# 11_MT7688AN_Ethernet.net
KiCad netlist of a schematic drawn in Altium Designer
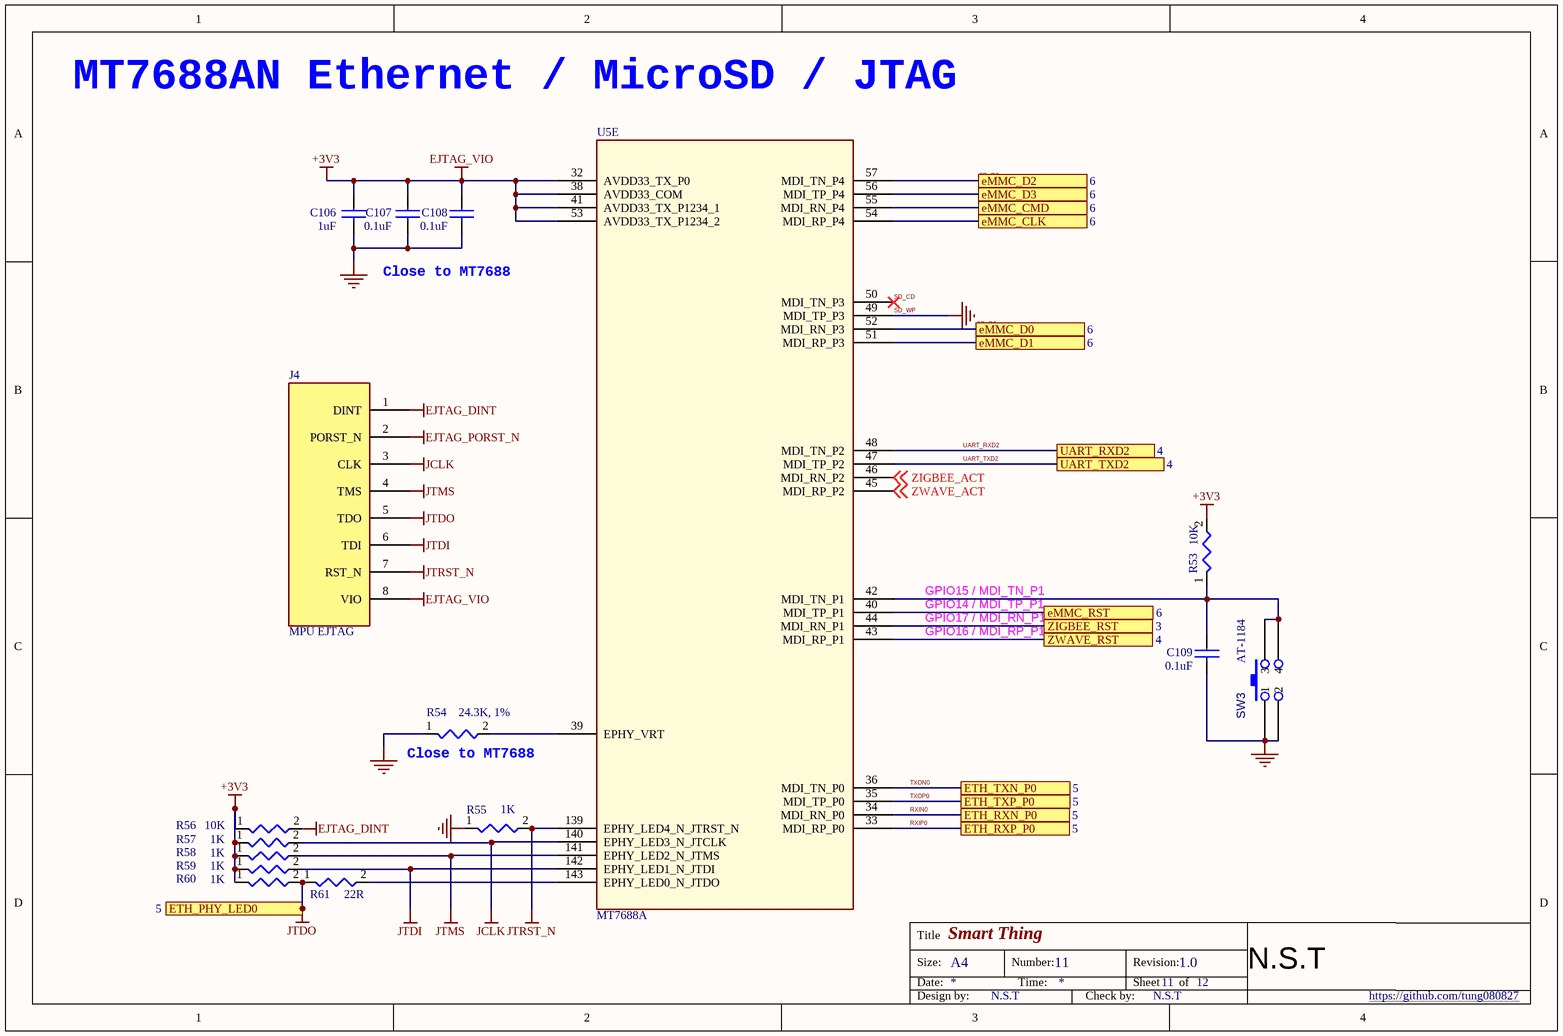
[diagram p0: 11. MT7688AN Ethernet.SchDoc]

(export (version "E")
  (design (tool "Eeschema 10.0.6"))
  (components
    (comp (ref "C106")
      (value "1uF")
      (footprint "CAPC1005X60X30NL05T10")
      (libsource (lib "MT7688AN") (part "CAP NP"))
    )
    (comp (ref "C107")
      (value "0.1uF")
      (footprint "CAPC1005X60X30NL05T10")
      (libsource (lib "MT7688AN") (part "CAP NP"))
    )
    (comp (ref "C108")
      (value "0.1uF")
      (footprint "CAPC1005X60X30NL05T10")
      (libsource (lib "MT7688AN") (part "CAP NP"))
    )
    (comp (ref "C109")
      (value "0.1uF")
      (footprint "CAPC1005X60X30NL05T10")
      (libsource (lib "MT7688AN") (part "CAP NP"))
    )
    (comp (ref "J4")
      (value "MPU EJTAG")
      (footprint "MPU EJTAG DEBUG")
      (libsource (lib "MT7688AN") (part "MPU EJTAG"))
    )
    (comp (ref "R53")
      (value "10K")
      (footprint "RESC1005X35X25NL10T10")
      (libsource (lib "MT7688AN") (part "RES/0402_3"))
    )
    (comp (ref "R54")
      (value "24.3K, 1%")
      (footprint "RESC1005X35X25NL10T10")
      (libsource (lib "MT7688AN") (part "RES/0402_3"))
    )
    (comp (ref "R55")
      (value "1K")
      (footprint "RESC1005X35X25NL10T10")
      (libsource (lib "MT7688AN") (part "RES/0402_3"))
    )
    (comp (ref "R56")
      (value "10K")
      (footprint "RESC1005X35X25NL10T10")
      (libsource (lib "MT7688AN") (part "RES/0402_3"))
    )
    (comp (ref "R57")
      (value "1K")
      (footprint "RESC1005X35X25NL10T10")
      (libsource (lib "MT7688AN") (part "RES/0402_3"))
    )
    (comp (ref "R58")
      (value "1K")
      (footprint "RESC1005X35X25NL10T10")
      (libsource (lib "MT7688AN") (part "RES/0402_3"))
    )
    (comp (ref "R59")
      (value "1K")
      (footprint "RESC1005X35X25NL10T10")
      (libsource (lib "MT7688AN") (part "RES/0402_3"))
    )
    (comp (ref "R60")
      (value "1K")
      (footprint "RESC1005X35X25NL10T10")
      (libsource (lib "MT7688AN") (part "RES/0402_3"))
    )
    (comp (ref "R61")
      (value "22R")
      (footprint "RESC1005X35X25NL10T10")
      (libsource (lib "MT7688AN") (part "RES/0402_3"))
    )
    (comp (ref "SW3")
      (value "AT-1184")
      (footprint "AT-1184 SW")
      (description "TACT Switch, H=1.5mm")
      (fields (field (name "MANUFACTURER") "Panasonic - ECG"))
      (libsource (lib "MT7688AN") (part "SW"))
    )
    (comp (ref "U5")
      (value "MT7688A")
      (footprint "MT7628AN$2F$DRQFN156$2F$SMD$2F$P0.5$2F$12X12")
      (libsource (lib "MT7688AN") (part "MT7620N-n_26"))
    )
  )
  (nets
    (net (code "1") (name "+3V3") (class "Default")
      (node (ref "C106") (pin "1") (pinfunction "1_1") (pintype "passive"))
      (node (ref "C107") (pin "1") (pinfunction "1_1") (pintype "passive"))
      (node (ref "C108") (pin "1") (pinfunction "1_1") (pintype "passive"))
      (node (ref "J4") (pin "8") (pinfunction "VIO_8") (pintype "passive"))
      (node (ref "R53") (pin "2") (pinfunction "2_2") (pintype "passive"))
      (node (ref "R56") (pin "1") (pinfunction "1_1") (pintype "passive"))
      (node (ref "R57") (pin "1") (pinfunction "1_1") (pintype "passive"))
      (node (ref "R58") (pin "1") (pinfunction "1_1") (pintype "passive"))
      (node (ref "R59") (pin "1") (pinfunction "1_1") (pintype "passive"))
      (node (ref "R60") (pin "1") (pinfunction "1_1") (pintype "passive"))
      (node (ref "U5") (pin "32") (pinfunction "AVDD33_TX_P0_32") (pintype "power_in"))
      (node (ref "U5") (pin "38") (pinfunction "AVDD33_COM_38") (pintype "power_in"))
      (node (ref "U5") (pin "41") (pinfunction "AVDD33_TX_P1234_1_41") (pintype "power_in"))
      (node (ref "U5") (pin "53") (pinfunction "AVDD33_TX_P1234_2_53") (pintype "power_in"))
    )
    (net (code "2") (name "/GPIO14 {slash} MDI_TP_P1") (class "Default")
      (node (ref "U5") (pin "40") (pinfunction "MDI_TP_P1_40") (pintype "passive"))
    )
    (net (code "3") (name "/GPIO15 {slash} MDI_TN_P1") (class "Default")
      (node (ref "C109") (pin "1") (pinfunction "1_1") (pintype "passive"))
      (node (ref "R53") (pin "1") (pinfunction "1_1") (pintype "passive"))
      (node (ref "SW3") (pin "3") (pinfunction "3_3") (pintype "passive"))
      (node (ref "SW3") (pin "4") (pinfunction "4_4") (pintype "passive"))
      (node (ref "U5") (pin "42") (pinfunction "MDI_TN_P1_42") (pintype "passive"))
    )
    (net (code "4") (name "/GPIO16 {slash} MDI_RP_P1") (class "Default")
      (node (ref "U5") (pin "43") (pinfunction "MDI_RP_P1_43") (pintype "passive"))
    )
    (net (code "5") (name "/GPIO17 {slash} MDI_RN_P1") (class "Default")
      (node (ref "U5") (pin "44") (pinfunction "MDI_RN_P1_44") (pintype "passive"))
    )
    (net (code "6") (name "/RXIN0") (class "Default")
      (node (ref "U5") (pin "34") (pinfunction "MDI_RN_P0_34") (pintype "passive"))
    )
    (net (code "7") (name "/RXIP0") (class "Default")
      (node (ref "U5") (pin "33") (pinfunction "MDI_RP_P0_33") (pintype "passive"))
    )
    (net (code "8") (name "/SD_CD") (class "Default")
      (node (ref "U5") (pin "50") (pinfunction "MDI_TN_P3_50") (pintype "passive+no_connect"))
    )
    (net (code "9") (name "/SD_CLK") (class "Default")
      (node (ref "U5") (pin "54") (pinfunction "MDI_RP_P4_54") (pintype "passive"))
    )
    (net (code "10") (name "/SD_CMD") (class "Default")
      (node (ref "U5") (pin "55") (pinfunction "MDI_RN_P4_55") (pintype "passive"))
    )
    (net (code "11") (name "/SD_D0") (class "Default")
      (node (ref "U5") (pin "52") (pinfunction "MDI_RN_P3_52") (pintype "passive"))
    )
    (net (code "12") (name "/SD_D1") (class "Default")
      (node (ref "U5") (pin "51") (pinfunction "MDI_RP_P3_51") (pintype "passive"))
    )
    (net (code "13") (name "/SD_D2") (class "Default")
      (node (ref "U5") (pin "57") (pinfunction "MDI_TN_P4_57") (pintype "passive"))
    )
    (net (code "14") (name "/SD_D3") (class "Default")
      (node (ref "U5") (pin "56") (pinfunction "MDI_TP_P4_56") (pintype "passive"))
    )
    (net (code "15") (name "/TXON0") (class "Default")
      (node (ref "U5") (pin "36") (pinfunction "MDI_TN_P0_36") (pintype "passive"))
    )
    (net (code "16") (name "/TXOP0") (class "Default")
      (node (ref "U5") (pin "35") (pinfunction "MDI_TP_P0_35") (pintype "passive"))
    )
    (net (code "17") (name "/UART_RXD2") (class "Default")
      (node (ref "U5") (pin "48") (pinfunction "MDI_TN_P2_48") (pintype "passive"))
    )
    (net (code "18") (name "/UART_TXD2") (class "Default")
      (node (ref "U5") (pin "47") (pinfunction "MDI_TP_P2_47") (pintype "passive"))
    )
    (net (code "19") (name "EJTAG_DINT") (class "Default")
      (node (ref "J4") (pin "1") (pinfunction "DINT_1") (pintype "passive"))
      (node (ref "R56") (pin "2") (pinfunction "2_2") (pintype "passive"))
    )
    (net (code "20") (name "EJTAG_PORST_N") (class "Default")
      (node (ref "J4") (pin "2") (pinfunction "PORST_N_2") (pintype "passive"))
    )
    (net (code "21") (name "GND") (class "Default")
      (node (ref "C106") (pin "2") (pinfunction "2_2") (pintype "passive"))
      (node (ref "C107") (pin "2") (pinfunction "2_2") (pintype "passive"))
      (node (ref "C108") (pin "2") (pinfunction "2_2") (pintype "passive"))
      (node (ref "C109") (pin "2") (pinfunction "2_2") (pintype "passive"))
      (node (ref "R54") (pin "1") (pinfunction "1_1") (pintype "passive"))
      (node (ref "R55") (pin "1") (pinfunction "1_1") (pintype "passive"))
      (node (ref "SW3") (pin "1") (pinfunction "1_1") (pintype "passive"))
      (node (ref "SW3") (pin "2") (pinfunction "2_2") (pintype "passive"))
      (node (ref "U5") (pin "49") (pinfunction "MDI_TP_P3_49") (pintype "passive"))
    )
    (net (code "22") (name "JCLK") (class "Default")
      (node (ref "J4") (pin "3") (pinfunction "CLK_3") (pintype "passive"))
      (node (ref "R57") (pin "2") (pinfunction "2_2") (pintype "passive"))
      (node (ref "U5") (pin "140") (pinfunction "EPHY_LED3_N_JTCLK_140") (pintype "passive"))
    )
    (net (code "23") (name "JTDI") (class "Default")
      (node (ref "J4") (pin "6") (pinfunction "TDI_6") (pintype "passive"))
      (node (ref "R59") (pin "2") (pinfunction "2_2") (pintype "passive"))
      (node (ref "U5") (pin "142") (pinfunction "EPHY_LED1_N_JTDI_142") (pintype "passive"))
    )
    (net (code "24") (name "JTDO") (class "Default")
      (node (ref "J4") (pin "5") (pinfunction "TDO_5") (pintype "passive"))
      (node (ref "R60") (pin "2") (pinfunction "2_2") (pintype "passive"))
      (node (ref "R61") (pin "1") (pinfunction "1_1") (pintype "passive"))
    )
    (net (code "25") (name "JTMS") (class "Default")
      (node (ref "J4") (pin "4") (pinfunction "TMS_4") (pintype "passive"))
      (node (ref "R58") (pin "2") (pinfunction "2_2") (pintype "passive"))
      (node (ref "U5") (pin "141") (pinfunction "EPHY_LED2_N_JTMS_141") (pintype "passive"))
    )
    (net (code "26") (name "JTRST_N") (class "Default")
      (node (ref "J4") (pin "7") (pinfunction "RST_N_7") (pintype "passive"))
      (node (ref "R55") (pin "2") (pinfunction "2_2") (pintype "passive"))
      (node (ref "U5") (pin "139") (pinfunction "EPHY_LED4_N_JTRST_N_139") (pintype "passive"))
    )
    (net (code "27") (name "Net-(U5E-EPHY_LED0_N_JTDO)") (class "Default")
      (node (ref "R61") (pin "2") (pinfunction "2_2") (pintype "passive"))
      (node (ref "U5") (pin "143") (pinfunction "EPHY_LED0_N_JTDO_143") (pintype "passive"))
    )
    (net (code "28") (name "Net-(U5E-EPHY_VRT)") (class "Default")
      (node (ref "R54") (pin "2") (pinfunction "2_2") (pintype "passive"))
      (node (ref "U5") (pin "39") (pinfunction "EPHY_VRT_39") (pintype "passive"))
    )
    (net (code "29") (name "ZIGBEE_ACT") (class "Default")
      (node (ref "U5") (pin "46") (pinfunction "MDI_RN_P2_46") (pintype "passive"))
    )
    (net (code "30") (name "ZWAVE_ACT") (class "Default")
      (node (ref "U5") (pin "45") (pinfunction "MDI_RP_P2_45") (pintype "passive"))
    )
  )
)
